# pir_breakout.net
KiCad netlist of a schematic drawn in EAGLE
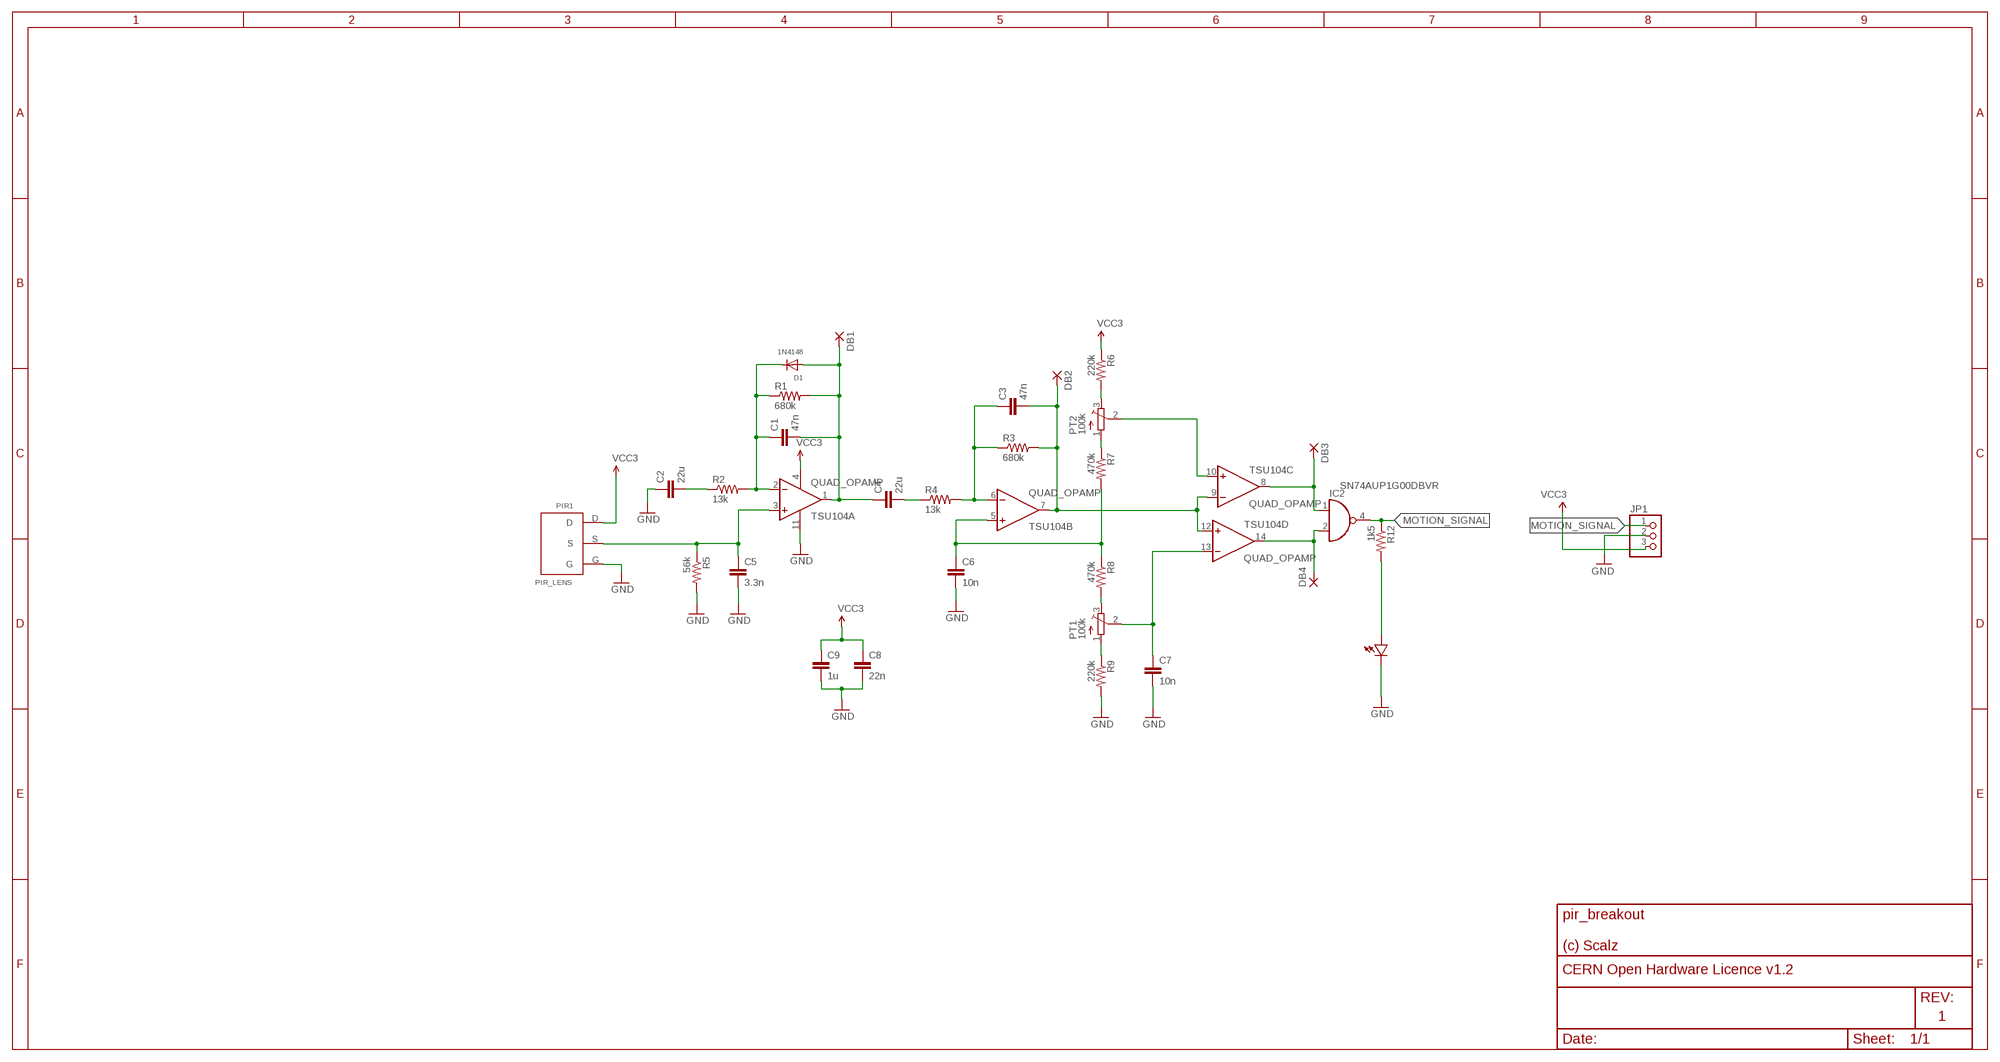
[diagram p0: schematic, sheet 1]

(export (version "E")
  (design (tool "Eeschema 10.0.6"))
  (components
    (comp (ref "C1")
      (value "47n")
      (footprint "eagle-import:0805-CAP")
      (libsource (lib "eagle-import") (part "CAP0805-CAP"))
    )
    (comp (ref "C2")
      (value "22u")
      (footprint "eagle-import:0805-CAP")
      (libsource (lib "eagle-import") (part "CAP0805-CAP"))
    )
    (comp (ref "C3")
      (value "47n")
      (footprint "eagle-import:0805-CAP")
      (libsource (lib "eagle-import") (part "CAP0805-CAP"))
    )
    (comp (ref "C4")
      (value "22u")
      (footprint "eagle-import:0805-CAP")
      (libsource (lib "eagle-import") (part "CAP0805-CAP"))
    )
    (comp (ref "C5")
      (value "3.3n")
      (footprint "eagle-import:0805-CAP")
      (libsource (lib "eagle-import") (part "CAP0805-CAP"))
    )
    (comp (ref "C6")
      (value "10n")
      (footprint "eagle-import:0805-CAP")
      (libsource (lib "eagle-import") (part "CAP0805-CAP"))
    )
    (comp (ref "C7")
      (value "10n")
      (footprint "eagle-import:0805-CAP")
      (libsource (lib "eagle-import") (part "CAP0805-CAP"))
    )
    (comp (ref "C8")
      (value "22n")
      (footprint "eagle-import:0805-CAP")
      (libsource (lib "eagle-import") (part "CAP0805-CAP"))
    )
    (comp (ref "C9")
      (value "1u")
      (footprint "eagle-import:0805-CAP")
      (libsource (lib "eagle-import") (part "CAP0805-CAP"))
    )
    (comp (ref "D1")
      (value "1N4148")
      (footprint "eagle-import:SOD-123")
      (libsource (lib "eagle-import") (part "DIODESOD-123"))
    )
    (comp (ref "D2")
      (value "LED0805")
      (footprint "eagle-import:0805-LED")
      (libsource (lib "eagle-import") (part "LED0805"))
    )
    (comp (ref "DB1")
      (value "1,6/0,8")
      (footprint "eagle-import:1,6_0,8")
      (libsource (lib "eagle-import") (part "1,6/0,8"))
    )
    (comp (ref "DB2")
      (value "1,6/0,8")
      (footprint "eagle-import:1,6_0,8")
      (libsource (lib "eagle-import") (part "1,6/0,8"))
    )
    (comp (ref "DB3")
      (value "1,6/0,8")
      (footprint "eagle-import:1,6_0,8")
      (libsource (lib "eagle-import") (part "1,6/0,8"))
    )
    (comp (ref "DB4")
      (value "1,6/0,8")
      (footprint "eagle-import:1,6_0,8")
      (libsource (lib "eagle-import") (part "1,6/0,8"))
    )
    (comp (ref "IC2")
      (value "SN74AUP1G00DBVR")
      (footprint "eagle-import:SOT23-5")
      (libsource (lib "eagle-import") (part "741G00DBVAHC"))
    )
    (comp (ref "JP1")
      (value "PINHD-1X3")
      (footprint "eagle-import:1X03")
      (libsource (lib "eagle-import") (part "PINHD-1X3"))
    )
    (comp (ref "PIR1")
      (value "PIR_LENS")
      (footprint "eagle-import:PIR_LENS")
      (libsource (lib "eagle-import") (part "PIR_LENS"))
    )
    (comp (ref "PT1")
      (value "100k")
      (footprint "eagle-import:TC33X")
      (libsource (lib "eagle-import") (part "TRIMPOTTC33X"))
    )
    (comp (ref "PT2")
      (value "100k")
      (footprint "eagle-import:TC33X")
      (libsource (lib "eagle-import") (part "TRIMPOTTC33X"))
    )
    (comp (ref "R1")
      (value "680k")
      (footprint "eagle-import:0805-RES")
      (libsource (lib "eagle-import") (part "RESISTOR0805-RES"))
    )
    (comp (ref "R2")
      (value "13k")
      (footprint "eagle-import:0805-RES")
      (libsource (lib "eagle-import") (part "RESISTOR0805-RES"))
    )
    (comp (ref "R3")
      (value "680k")
      (footprint "eagle-import:0805-RES")
      (libsource (lib "eagle-import") (part "RESISTOR0805-RES"))
    )
    (comp (ref "R4")
      (value "13k")
      (footprint "eagle-import:0805-RES")
      (libsource (lib "eagle-import") (part "RESISTOR0805-RES"))
    )
    (comp (ref "R5")
      (value "56k")
      (footprint "eagle-import:0805-RES")
      (libsource (lib "eagle-import") (part "RESISTOR0805-RES"))
    )
    (comp (ref "R6")
      (value "220k")
      (footprint "eagle-import:0805-RES")
      (libsource (lib "eagle-import") (part "RESISTOR0805-RES"))
    )
    (comp (ref "R7")
      (value "470k")
      (footprint "eagle-import:0805-RES")
      (libsource (lib "eagle-import") (part "RESISTOR0805-RES"))
    )
    (comp (ref "R8")
      (value "470k")
      (footprint "eagle-import:0805-RES")
      (libsource (lib "eagle-import") (part "RESISTOR0805-RES"))
    )
    (comp (ref "R9")
      (value "220k")
      (footprint "eagle-import:0805-RES")
      (libsource (lib "eagle-import") (part "RESISTOR0805-RES"))
    )
    (comp (ref "R12")
      (value "1k5")
      (footprint "eagle-import:0805-RES")
      (libsource (lib "eagle-import") (part "RESISTOR0805-RES"))
    )
    (comp (ref "TSU104")
      (value "QUAD_OPAMP")
      (footprint "eagle-import:TSSOP-14")
      (libsource (lib "eagle-import") (part "QUAD_OPAMP"))
    )
  )
  (nets
    (net (code "1") (name "GND") (class "Default")
      (node (ref "C2") (pin "1") (pinfunction "1_1") (pintype "passive"))
      (node (ref "C5") (pin "2") (pinfunction "2_2") (pintype "passive"))
      (node (ref "C6") (pin "2") (pinfunction "2_2") (pintype "passive"))
      (node (ref "C7") (pin "2") (pinfunction "2_2") (pintype "passive"))
      (node (ref "C8") (pin "2") (pinfunction "2_2") (pintype "passive"))
      (node (ref "C9") (pin "2") (pinfunction "2_2") (pintype "passive"))
      (node (ref "D2") (pin "MINUS") (pinfunction "MINUS_MINUS") (pintype "passive"))
      (node (ref "JP1") (pin "2") (pinfunction "2_2") (pintype "passive"))
      (node (ref "PIR1") (pin "G") (pinfunction "G_G") (pintype "bidirectional"))
      (node (ref "R5") (pin "2") (pinfunction "2_2") (pintype "passive"))
      (node (ref "R9") (pin "2") (pinfunction "2_2") (pintype "passive"))
      (node (ref "TSU104") (pin "11") (pinfunction "V-_11") (pintype "power_in"))
    )
    (net (code "2") (name "MOTION_SIGNAL") (class "Default")
      (node (ref "IC2") (pin "4") (pinfunction "O_4") (pintype "output"))
      (node (ref "JP1") (pin "1") (pinfunction "1_1") (pintype "passive"))
      (node (ref "R12") (pin "1") (pinfunction "1_1") (pintype "passive"))
    )
    (net (code "3") (name "Net-(C2-Pad2)") (class "Default")
      (node (ref "C2") (pin "2") (pinfunction "2_2") (pintype "passive"))
      (node (ref "R2") (pin "1") (pinfunction "1_1") (pintype "passive"))
    )
    (net (code "4") (name "Net-(C4-Pad2)") (class "Default")
      (node (ref "C4") (pin "2") (pinfunction "2_2") (pintype "passive"))
      (node (ref "R4") (pin "1") (pinfunction "1_1") (pintype "passive"))
    )
    (net (code "5") (name "Net-(D2-PadPLUS)") (class "Default")
      (node (ref "D2") (pin "PLUS") (pinfunction "PLUS_PLUS") (pintype "passive"))
      (node (ref "R12") (pin "2") (pinfunction "2_2") (pintype "passive"))
    )
    (net (code "6") (name "Net-(DB1-P)") (class "Default")
      (node (ref "C1") (pin "2") (pinfunction "2_2") (pintype "passive"))
      (node (ref "C4") (pin "1") (pinfunction "1_1") (pintype "passive"))
      (node (ref "D1") (pin "A") (pinfunction "A_A") (pintype "passive"))
      (node (ref "DB1") (pin "1") (pinfunction "P_1") (pintype "passive"))
      (node (ref "R1") (pin "2") (pinfunction "2_2") (pintype "passive"))
      (node (ref "TSU104") (pin "1") (pinfunction "OUT_1") (pintype "output"))
    )
    (net (code "7") (name "Net-(DB2-P)") (class "Default")
      (node (ref "C3") (pin "2") (pinfunction "2_2") (pintype "passive"))
      (node (ref "DB2") (pin "1") (pinfunction "P_1") (pintype "passive"))
      (node (ref "R3") (pin "2") (pinfunction "2_2") (pintype "passive"))
      (node (ref "TSU104") (pin "12") (pinfunction "+IN_12") (pintype "input"))
      (node (ref "TSU104") (pin "7") (pinfunction "OUT_7") (pintype "output"))
      (node (ref "TSU104") (pin "9") (pinfunction "-IN_9") (pintype "input"))
    )
    (net (code "8") (name "Net-(DB3-P)") (class "Default")
      (node (ref "DB3") (pin "1") (pinfunction "P_1") (pintype "passive"))
      (node (ref "IC2") (pin "1") (pinfunction "I0_1") (pintype "input"))
      (node (ref "TSU104") (pin "8") (pinfunction "OUT_8") (pintype "output"))
    )
    (net (code "9") (name "Net-(DB4-P)") (class "Default")
      (node (ref "DB4") (pin "1") (pinfunction "P_1") (pintype "passive"))
      (node (ref "IC2") (pin "2") (pinfunction "I1_2") (pintype "input"))
      (node (ref "TSU104") (pin "14") (pinfunction "OUT_14") (pintype "output"))
    )
    (net (code "10") (name "Net-(PT1-A)") (class "Default")
      (node (ref "PT1") (pin "1") (pinfunction "A_1") (pintype "passive"))
      (node (ref "R9") (pin "1") (pinfunction "1_1") (pintype "passive"))
    )
    (net (code "11") (name "Net-(PT1-E)") (class "Default")
      (node (ref "PT1") (pin "3") (pinfunction "E_3") (pintype "passive"))
      (node (ref "R8") (pin "2") (pinfunction "2_2") (pintype "passive"))
    )
    (net (code "12") (name "Net-(PT1-S)") (class "Default")
      (node (ref "C7") (pin "1") (pinfunction "1_1") (pintype "passive"))
      (node (ref "PT1") (pin "2") (pinfunction "S_2") (pintype "passive"))
      (node (ref "TSU104") (pin "13") (pinfunction "-IN_13") (pintype "input"))
    )
    (net (code "13") (name "Net-(PT2-A)") (class "Default")
      (node (ref "PT2") (pin "1") (pinfunction "A_1") (pintype "passive"))
      (node (ref "R7") (pin "1") (pinfunction "1_1") (pintype "passive"))
    )
    (net (code "14") (name "Net-(PT2-E)") (class "Default")
      (node (ref "PT2") (pin "3") (pinfunction "E_3") (pintype "passive"))
      (node (ref "R6") (pin "2") (pinfunction "2_2") (pintype "passive"))
    )
    (net (code "15") (name "Net-(PT2-S)") (class "Default")
      (node (ref "PT2") (pin "2") (pinfunction "S_2") (pintype "passive"))
      (node (ref "TSU104") (pin "10") (pinfunction "+IN_10") (pintype "input"))
    )
    (net (code "16") (name "Net-(TSU104A-+IN)") (class "Default")
      (node (ref "C5") (pin "1") (pinfunction "1_1") (pintype "passive"))
      (node (ref "PIR1") (pin "S") (pinfunction "S_S") (pintype "bidirectional"))
      (node (ref "R5") (pin "1") (pinfunction "1_1") (pintype "passive"))
      (node (ref "TSU104") (pin "3") (pinfunction "+IN_3") (pintype "input"))
    )
    (net (code "17") (name "Net-(TSU104A--IN)") (class "Default")
      (node (ref "C1") (pin "1") (pinfunction "1_1") (pintype "passive"))
      (node (ref "D1") (pin "C") (pinfunction "C_C") (pintype "passive"))
      (node (ref "R1") (pin "1") (pinfunction "1_1") (pintype "passive"))
      (node (ref "R2") (pin "2") (pinfunction "2_2") (pintype "passive"))
      (node (ref "TSU104") (pin "2") (pinfunction "-IN_2") (pintype "input"))
    )
    (net (code "18") (name "Net-(TSU104B-+IN)") (class "Default")
      (node (ref "C6") (pin "1") (pinfunction "1_1") (pintype "passive"))
      (node (ref "R7") (pin "2") (pinfunction "2_2") (pintype "passive"))
      (node (ref "R8") (pin "1") (pinfunction "1_1") (pintype "passive"))
      (node (ref "TSU104") (pin "5") (pinfunction "+IN_5") (pintype "input"))
    )
    (net (code "19") (name "Net-(TSU104B--IN)") (class "Default")
      (node (ref "C3") (pin "1") (pinfunction "1_1") (pintype "passive"))
      (node (ref "R3") (pin "1") (pinfunction "1_1") (pintype "passive"))
      (node (ref "R4") (pin "2") (pinfunction "2_2") (pintype "passive"))
      (node (ref "TSU104") (pin "6") (pinfunction "-IN_6") (pintype "input"))
    )
    (net (code "20") (name "VCC3") (class "Default")
      (node (ref "C8") (pin "1") (pinfunction "1_1") (pintype "passive"))
      (node (ref "C9") (pin "1") (pinfunction "1_1") (pintype "passive"))
      (node (ref "JP1") (pin "3") (pinfunction "3_3") (pintype "passive"))
      (node (ref "PIR1") (pin "D") (pinfunction "D_D") (pintype "bidirectional"))
      (node (ref "R6") (pin "1") (pinfunction "1_1") (pintype "passive"))
      (node (ref "TSU104") (pin "4") (pinfunction "V+_4") (pintype "power_in"))
    )
  )
)
